# Mako_DSP_Audio_Codec_R1_2.net
KiCad netlist of a schematic drawn in Altium Designer
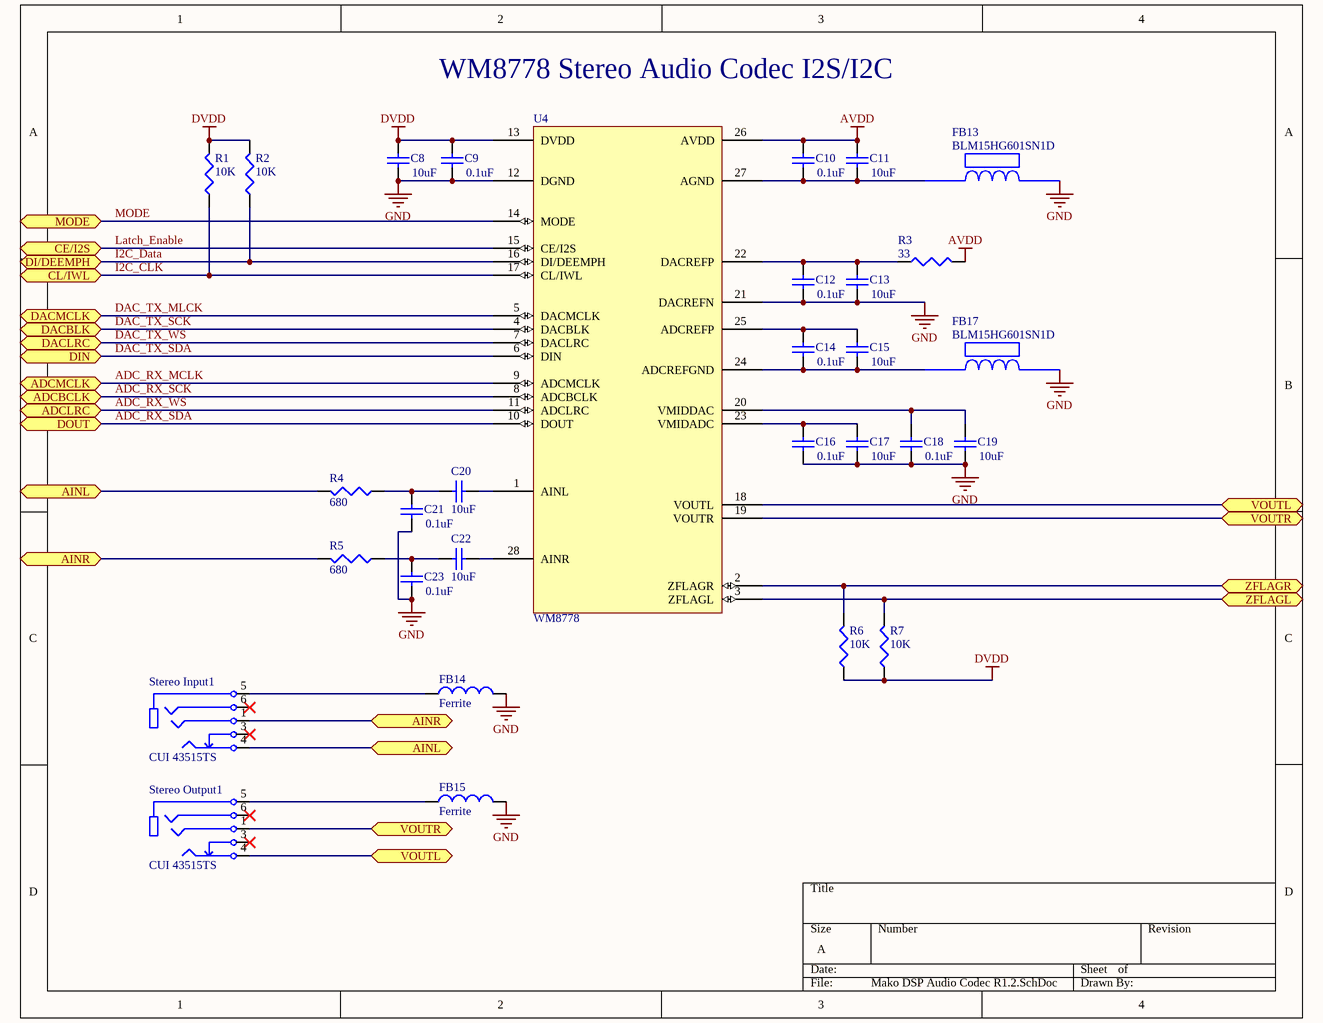
[diagram p0: Mako DSP Audio Codec R1.2.SchDoc]

(export (version "E")
  (design (tool "Eeschema 10.0.6"))
  (components
    (comp (ref "C8")
      (value "10uF")
      (footprint "1608[0603]")
      (description "Capacitor (Semiconductor SIM Model)")
      (fields (field (name "Comment") "Cap Semi") (field (name "PUBLISHER") "Altium Limited"))
      (libsource (lib "Miscellaneous Devices") (part "Cap Semi"))
    )
    (comp (ref "C9")
      (value "0.1uF")
      (footprint "1608[0603]")
      (description "Capacitor (Semiconductor SIM Model)")
      (fields (field (name "Comment") "Cap Semi") (field (name "PUBLISHER") "Altium Limited"))
      (libsource (lib "Miscellaneous Devices") (part "Cap Semi"))
    )
    (comp (ref "C10")
      (value "0.1uF")
      (footprint "1608[0603]")
      (description "Capacitor (Semiconductor SIM Model)")
      (fields (field (name "Comment") "Cap Semi") (field (name "PUBLISHER") "Altium Limited"))
      (libsource (lib "Miscellaneous Devices") (part "Cap Semi"))
    )
    (comp (ref "C11")
      (value "10uF")
      (footprint "1608[0603]")
      (description "Capacitor (Semiconductor SIM Model)")
      (fields (field (name "Comment") "Cap Semi") (field (name "PUBLISHER") "Altium Limited"))
      (libsource (lib "Miscellaneous Devices") (part "Cap Semi"))
    )
    (comp (ref "C12")
      (value "0.1uF")
      (footprint "1608[0603]")
      (description "Capacitor (Semiconductor SIM Model)")
      (fields (field (name "Comment") "Cap Semi") (field (name "PUBLISHER") "Altium Limited"))
      (libsource (lib "Miscellaneous Devices") (part "Cap Semi"))
    )
    (comp (ref "C13")
      (value "10uF")
      (footprint "1608[0603]")
      (description "Capacitor (Semiconductor SIM Model)")
      (fields (field (name "Comment") "Cap Semi") (field (name "PUBLISHER") "Altium Limited"))
      (libsource (lib "Miscellaneous Devices") (part "Cap Semi"))
    )
    (comp (ref "C14")
      (value "0.1uF")
      (footprint "1608[0603]")
      (description "Capacitor (Semiconductor SIM Model)")
      (fields (field (name "Comment") "Cap Semi") (field (name "PUBLISHER") "Altium Limited"))
      (libsource (lib "Miscellaneous Devices") (part "Cap Semi"))
    )
    (comp (ref "C15")
      (value "10uF")
      (footprint "1608[0603]")
      (description "Capacitor (Semiconductor SIM Model)")
      (fields (field (name "Comment") "Cap Semi") (field (name "PUBLISHER") "Altium Limited"))
      (libsource (lib "Miscellaneous Devices") (part "Cap Semi"))
    )
    (comp (ref "C16")
      (value "0.1uF")
      (footprint "1608[0603]")
      (description "Capacitor (Semiconductor SIM Model)")
      (fields (field (name "Comment") "Cap Semi") (field (name "PUBLISHER") "Altium Limited"))
      (libsource (lib "Miscellaneous Devices") (part "Cap Semi"))
    )
    (comp (ref "C17")
      (value "10uF")
      (footprint "1608[0603]")
      (description "Capacitor (Semiconductor SIM Model)")
      (fields (field (name "Comment") "Cap Semi") (field (name "PUBLISHER") "Altium Limited"))
      (libsource (lib "Miscellaneous Devices") (part "Cap Semi"))
    )
    (comp (ref "C18")
      (value "0.1uF")
      (footprint "1608[0603]")
      (description "Capacitor (Semiconductor SIM Model)")
      (fields (field (name "Comment") "Cap Semi") (field (name "PUBLISHER") "Altium Limited"))
      (libsource (lib "Miscellaneous Devices") (part "Cap Semi"))
    )
    (comp (ref "C19")
      (value "10uF")
      (footprint "1608[0603]")
      (description "Capacitor (Semiconductor SIM Model)")
      (fields (field (name "Comment") "Cap Semi") (field (name "PUBLISHER") "Altium Limited"))
      (libsource (lib "Miscellaneous Devices") (part "Cap Semi"))
    )
    (comp (ref "C20")
      (value "10uF")
      (footprint "Panasonic VS B")
      (description "Capacitor (Semiconductor SIM Model)")
      (fields (field (name "Comment") "Cap Semi") (field (name "PUBLISHER") "Altium Limited"))
      (libsource (lib "Miscellaneous Devices") (part "Cap Semi"))
    )
    (comp (ref "C21")
      (value "0.1uF")
      (footprint "SM 0805 - gap trimmed")
      (description "Capacitor (Semiconductor SIM Model)")
      (fields (field (name "Comment") "Cap Semi") (field (name "PUBLISHER") "Altium Limited"))
      (libsource (lib "Miscellaneous Devices") (part "Cap Semi"))
    )
    (comp (ref "C22")
      (value "10uF")
      (footprint "Panasonic VS B")
      (description "Capacitor (Semiconductor SIM Model)")
      (fields (field (name "Comment") "Cap Semi") (field (name "PUBLISHER") "Altium Limited"))
      (libsource (lib "Miscellaneous Devices") (part "Cap Semi"))
    )
    (comp (ref "C23")
      (value "0.1uF")
      (footprint "SM 0805 - gap trimmed")
      (description "Capacitor (Semiconductor SIM Model)")
      (fields (field (name "Comment") "Cap Semi") (field (name "PUBLISHER") "Altium Limited"))
      (libsource (lib "Miscellaneous Devices") (part "Cap Semi"))
    )
    (comp (ref "FB13")
      (value "BLM15HG601SN1D")
      (footprint "BLM18PG121SN1D")
      (libsource (lib "AHD Part Library") (part "BLM15HG601SN1D"))
    )
    (comp (ref "FB14")
      (value "Ferrite")
      (footprint "SM 0805 - gap trimmed")
      (description "Inductor")
      (fields (field (name "PUBLISHER") "Altium Limited"))
      (libsource (lib "Miscellaneous Devices") (part "Inductor"))
    )
    (comp (ref "FB15")
      (value "Ferrite")
      (footprint "SM 0805 - gap trimmed")
      (description "Inductor")
      (fields (field (name "PUBLISHER") "Altium Limited"))
      (libsource (lib "Miscellaneous Devices") (part "Inductor"))
    )
    (comp (ref "FB17")
      (value "BLM15HG601SN1D")
      (footprint "BLM18PG121SN1D")
      (libsource (lib "AHD Part Library") (part "BLM15HG601SN1D"))
    )
    (comp (ref "R1")
      (value "10K")
      (footprint "J1-0603")
      (description "Resistor")
      (fields (field (name "Comment") "Res3") (field (name "PUBLISHER") "Altium Limited"))
      (libsource (lib "Miscellaneous Devices") (part "Res3"))
    )
    (comp (ref "R2")
      (value "10K")
      (footprint "J1-0603")
      (description "Resistor")
      (fields (field (name "Comment") "Res3") (field (name "PUBLISHER") "Altium Limited"))
      (libsource (lib "Miscellaneous Devices") (part "Res3"))
    )
    (comp (ref "R3")
      (value "33")
      (footprint "J1-0603")
      (description "Resistor")
      (fields (field (name "Comment") "Res3") (field (name "PUBLISHER") "Altium Limited"))
      (libsource (lib "Miscellaneous Devices") (part "Res3"))
    )
    (comp (ref "R4")
      (value "680")
      (footprint "SM 0805 - gap trimmed")
      (description "Resistor")
      (fields (field (name "Comment") "Res3") (field (name "PUBLISHER") "Altium Limited"))
      (libsource (lib "Miscellaneous Devices") (part "Res3"))
    )
    (comp (ref "R5")
      (value "680")
      (footprint "SM 0805 - gap trimmed")
      (description "Resistor")
      (fields (field (name "Comment") "Res3") (field (name "PUBLISHER") "Altium Limited"))
      (libsource (lib "Miscellaneous Devices") (part "Res3"))
    )
    (comp (ref "R6")
      (value "10K")
      (footprint "J1-0603")
      (description "Resistor")
      (fields (field (name "Comment") "Res3") (field (name "PUBLISHER") "Altium Limited"))
      (libsource (lib "Miscellaneous Devices") (part "Res3"))
    )
    (comp (ref "R7")
      (value "10K")
      (footprint "J1-0603")
      (description "Resistor")
      (fields (field (name "Comment") "Res3") (field (name "PUBLISHER") "Altium Limited"))
      (libsource (lib "Miscellaneous Devices") (part "Res3"))
    )
    (comp (ref "Stereo Input1")
      (value "CUI 43515TS")
      (footprint "CUI SJ-43515TS")
      (libsource (lib "Adams Altium Library") (part "CUI 43515TS"))
    )
    (comp (ref "Stereo Output1")
      (value "CUI 43515TS")
      (footprint "CUI SJ-43515TS")
      (libsource (lib "Adams Altium Library") (part "CUI 43515TS"))
    )
    (comp (ref "U4")
      (value "WM8778")
      (footprint "WM8778")
      (libsource (lib "Mako DSP Schematic Library") (part "WM8778"))
    )
  )
  (nets
    (net (code "1") (name "/ADC_RX_MCLK") (class "Default")
      (node (ref "U4") (pin "9") (pinfunction "ADCMCLK_9") (pintype "bidirectional"))
    )
    (net (code "2") (name "/ADC_RX_SCK") (class "Default")
      (node (ref "U4") (pin "8") (pinfunction "ADCBCLK_8") (pintype "bidirectional"))
    )
    (net (code "3") (name "/ADC_RX_SDA") (class "Default")
      (node (ref "U4") (pin "10") (pinfunction "DOUT_10") (pintype "bidirectional"))
    )
    (net (code "4") (name "/ADC_RX_WS") (class "Default")
      (node (ref "U4") (pin "11") (pinfunction "ADCLRC_11") (pintype "bidirectional"))
    )
    (net (code "5") (name "/AINL") (class "Default")
      (node (ref "R4") (pin "2") (pinfunction "2_2") (pintype "passive"))
      (node (ref "Stereo Input1") (pin "4") (pinfunction "TIP_4") (pintype "passive"))
    )
    (net (code "6") (name "/AINR") (class "Default")
      (node (ref "R5") (pin "2") (pinfunction "2_2") (pintype "passive"))
      (node (ref "Stereo Input1") (pin "1") (pinfunction "R1_1") (pintype "passive"))
    )
    (net (code "7") (name "/DAC_TX_MLCK") (class "Default")
      (node (ref "U4") (pin "5") (pinfunction "DACMCLK_5") (pintype "bidirectional"))
    )
    (net (code "8") (name "/DAC_TX_SCK") (class "Default")
      (node (ref "U4") (pin "4") (pinfunction "DACBLK_4") (pintype "bidirectional"))
    )
    (net (code "9") (name "/DAC_TX_SDA") (class "Default")
      (node (ref "U4") (pin "6") (pinfunction "DIN_6") (pintype "bidirectional"))
    )
    (net (code "10") (name "/DAC_TX_WS") (class "Default")
      (node (ref "U4") (pin "7") (pinfunction "DACLRC_7") (pintype "bidirectional"))
    )
    (net (code "11") (name "/I2C_CLK") (class "Default")
      (node (ref "R1") (pin "1") (pinfunction "1_1") (pintype "passive"))
      (node (ref "U4") (pin "17") (pinfunction "CL/IWL_17") (pintype "bidirectional"))
    )
    (net (code "12") (name "/I2C_Data") (class "Default")
      (node (ref "R2") (pin "1") (pinfunction "1_1") (pintype "passive"))
      (node (ref "U4") (pin "16") (pinfunction "DI/DEEMPH_16") (pintype "bidirectional"))
    )
    (net (code "13") (name "/Latch_Enable") (class "Default")
      (node (ref "U4") (pin "15") (pinfunction "CE/I2S_15") (pintype "bidirectional"))
    )
    (net (code "14") (name "/MODE") (class "Default")
      (node (ref "U4") (pin "14") (pinfunction "MODE_14") (pintype "bidirectional"))
    )
    (net (code "15") (name "/VOUTL") (class "Default")
      (node (ref "Stereo Output1") (pin "4") (pinfunction "TIP_4") (pintype "passive"))
      (node (ref "U4") (pin "18") (pinfunction "VOUTL_18") (pintype "passive"))
    )
    (net (code "16") (name "/VOUTR") (class "Default")
      (node (ref "Stereo Output1") (pin "1") (pinfunction "R1_1") (pintype "passive"))
      (node (ref "U4") (pin "19") (pinfunction "VOUTR_19") (pintype "passive"))
    )
    (net (code "17") (name "/ZFLAGL") (class "Default")
      (node (ref "R7") (pin "2") (pinfunction "2_2") (pintype "passive"))
      (node (ref "U4") (pin "3") (pinfunction "ZFLAGL_3") (pintype "bidirectional"))
    )
    (net (code "18") (name "/ZFLAGR") (class "Default")
      (node (ref "R6") (pin "2") (pinfunction "2_2") (pintype "passive"))
      (node (ref "U4") (pin "2") (pinfunction "ZFLAGR_2") (pintype "bidirectional"))
    )
    (net (code "19") (name "AVDD") (class "Default")
      (node (ref "C10") (pin "2") (pinfunction "2_2") (pintype "passive"))
      (node (ref "C11") (pin "2") (pinfunction "2_2") (pintype "passive"))
      (node (ref "R3") (pin "2") (pinfunction "2_2") (pintype "passive"))
      (node (ref "U4") (pin "26") (pinfunction "AVDD_26") (pintype "passive"))
    )
    (net (code "20") (name "DVDD") (class "Default")
      (node (ref "C8") (pin "2") (pinfunction "2_2") (pintype "passive"))
      (node (ref "C9") (pin "2") (pinfunction "2_2") (pintype "passive"))
      (node (ref "R1") (pin "2") (pinfunction "2_2") (pintype "passive"))
      (node (ref "R2") (pin "2") (pinfunction "2_2") (pintype "passive"))
      (node (ref "R6") (pin "1") (pinfunction "1_1") (pintype "passive"))
      (node (ref "R7") (pin "1") (pinfunction "1_1") (pintype "passive"))
      (node (ref "U4") (pin "13") (pinfunction "DVDD_13") (pintype "passive"))
    )
    (net (code "21") (name "GND") (class "Default")
      (node (ref "C12") (pin "1") (pinfunction "1_1") (pintype "passive"))
      (node (ref "C13") (pin "1") (pinfunction "1_1") (pintype "passive"))
      (node (ref "C16") (pin "1") (pinfunction "1_1") (pintype "passive"))
      (node (ref "C17") (pin "1") (pinfunction "1_1") (pintype "passive"))
      (node (ref "C18") (pin "1") (pinfunction "1_1") (pintype "passive"))
      (node (ref "C19") (pin "1") (pinfunction "1_1") (pintype "passive"))
      (node (ref "C21") (pin "1") (pinfunction "1_1") (pintype "passive"))
      (node (ref "C23") (pin "1") (pinfunction "1_1") (pintype "passive"))
      (node (ref "C8") (pin "1") (pinfunction "1_1") (pintype "passive"))
      (node (ref "C9") (pin "1") (pinfunction "1_1") (pintype "passive"))
      (node (ref "FB13") (pin "2") (pinfunction "2_2") (pintype "passive"))
      (node (ref "FB14") (pin "2") (pinfunction "2_2") (pintype "passive"))
      (node (ref "FB15") (pin "2") (pinfunction "2_2") (pintype "passive"))
      (node (ref "FB17") (pin "2") (pinfunction "2_2") (pintype "passive"))
      (node (ref "U4") (pin "12") (pinfunction "DGND_12") (pintype "passive"))
      (node (ref "U4") (pin "21") (pinfunction "DACREFN_21") (pintype "passive"))
    )
    (net (code "22") (name "Net-(C20-Pad2)") (class "Default")
      (node (ref "C20") (pin "2") (pinfunction "2_2") (pintype "passive"))
      (node (ref "C21") (pin "2") (pinfunction "2_2") (pintype "passive"))
      (node (ref "R4") (pin "1") (pinfunction "1_1") (pintype "passive"))
    )
    (net (code "23") (name "Net-(C22-Pad2)") (class "Default")
      (node (ref "C22") (pin "2") (pinfunction "2_2") (pintype "passive"))
      (node (ref "C23") (pin "2") (pinfunction "2_2") (pintype "passive"))
      (node (ref "R5") (pin "1") (pinfunction "1_1") (pintype "passive"))
    )
    (net (code "24") (name "Net-(Stereo Input1-SLEEVE)") (class "Default")
      (node (ref "FB14") (pin "1") (pinfunction "1_1") (pintype "passive"))
      (node (ref "Stereo Input1") (pin "5") (pinfunction "SLEEVE_5") (pintype "passive"))
    )
    (net (code "25") (name "Net-(Stereo Output1-SLEEVE)") (class "Default")
      (node (ref "FB15") (pin "1") (pinfunction "1_1") (pintype "passive"))
      (node (ref "Stereo Output1") (pin "5") (pinfunction "SLEEVE_5") (pintype "passive"))
    )
    (net (code "26") (name "Net-(U4-ADCREFGND)") (class "Default")
      (node (ref "C14") (pin "1") (pinfunction "1_1") (pintype "passive"))
      (node (ref "C15") (pin "1") (pinfunction "1_1") (pintype "passive"))
      (node (ref "FB17") (pin "1") (pinfunction "1_1") (pintype "passive"))
      (node (ref "U4") (pin "24") (pinfunction "ADCREFGND_24") (pintype "passive"))
    )
    (net (code "27") (name "Net-(U4-ADCREFP)") (class "Default")
      (node (ref "C14") (pin "2") (pinfunction "2_2") (pintype "passive"))
      (node (ref "C15") (pin "2") (pinfunction "2_2") (pintype "passive"))
      (node (ref "U4") (pin "25") (pinfunction "ADCREFP_25") (pintype "passive"))
    )
    (net (code "28") (name "Net-(U4-AGND)") (class "Default")
      (node (ref "C10") (pin "1") (pinfunction "1_1") (pintype "passive"))
      (node (ref "C11") (pin "1") (pinfunction "1_1") (pintype "passive"))
      (node (ref "FB13") (pin "1") (pinfunction "1_1") (pintype "passive"))
      (node (ref "U4") (pin "27") (pinfunction "AGND_27") (pintype "passive"))
    )
    (net (code "29") (name "Net-(U4-AINL)") (class "Default")
      (node (ref "C20") (pin "1") (pinfunction "1_1") (pintype "passive"))
      (node (ref "U4") (pin "1") (pinfunction "AINL_1") (pintype "passive"))
    )
    (net (code "30") (name "Net-(U4-AINR)") (class "Default")
      (node (ref "C22") (pin "1") (pinfunction "1_1") (pintype "passive"))
      (node (ref "U4") (pin "28") (pinfunction "AINR_28") (pintype "passive"))
    )
    (net (code "31") (name "Net-(U4-DACREFP)") (class "Default")
      (node (ref "C12") (pin "2") (pinfunction "2_2") (pintype "passive"))
      (node (ref "C13") (pin "2") (pinfunction "2_2") (pintype "passive"))
      (node (ref "R3") (pin "1") (pinfunction "1_1") (pintype "passive"))
      (node (ref "U4") (pin "22") (pinfunction "DACREFP_22") (pintype "passive"))
    )
    (net (code "32") (name "Net-(U4-VMIDADC)") (class "Default")
      (node (ref "C16") (pin "2") (pinfunction "2_2") (pintype "passive"))
      (node (ref "C17") (pin "2") (pinfunction "2_2") (pintype "passive"))
      (node (ref "U4") (pin "23") (pinfunction "VMIDADC_23") (pintype "passive"))
    )
    (net (code "33") (name "Net-(U4-VMIDDAC)") (class "Default")
      (node (ref "C18") (pin "2") (pinfunction "2_2") (pintype "passive"))
      (node (ref "C19") (pin "2") (pinfunction "2_2") (pintype "passive"))
      (node (ref "U4") (pin "20") (pinfunction "VMIDDAC_20") (pintype "passive"))
    )
    (net (code "34") (name "unconnected-(Stereo Input1-R2-Pad6)") (class "Default")
      (node (ref "Stereo Input1") (pin "6") (pinfunction "R2_6") (pintype "passive+no_connect"))
    )
    (net (code "35") (name "unconnected-(Stereo Input1-TS-Pad3)") (class "Default")
      (node (ref "Stereo Input1") (pin "3") (pinfunction "TS_3") (pintype "passive+no_connect"))
    )
    (net (code "36") (name "unconnected-(Stereo Output1-R2-Pad6)") (class "Default")
      (node (ref "Stereo Output1") (pin "6") (pinfunction "R2_6") (pintype "passive+no_connect"))
    )
    (net (code "37") (name "unconnected-(Stereo Output1-TS-Pad3)") (class "Default")
      (node (ref "Stereo Output1") (pin "3") (pinfunction "TS_3") (pintype "passive+no_connect"))
    )
  )
)
